# 7006268-0.net
KiCad netlist of a schematic drawn in EAGLE
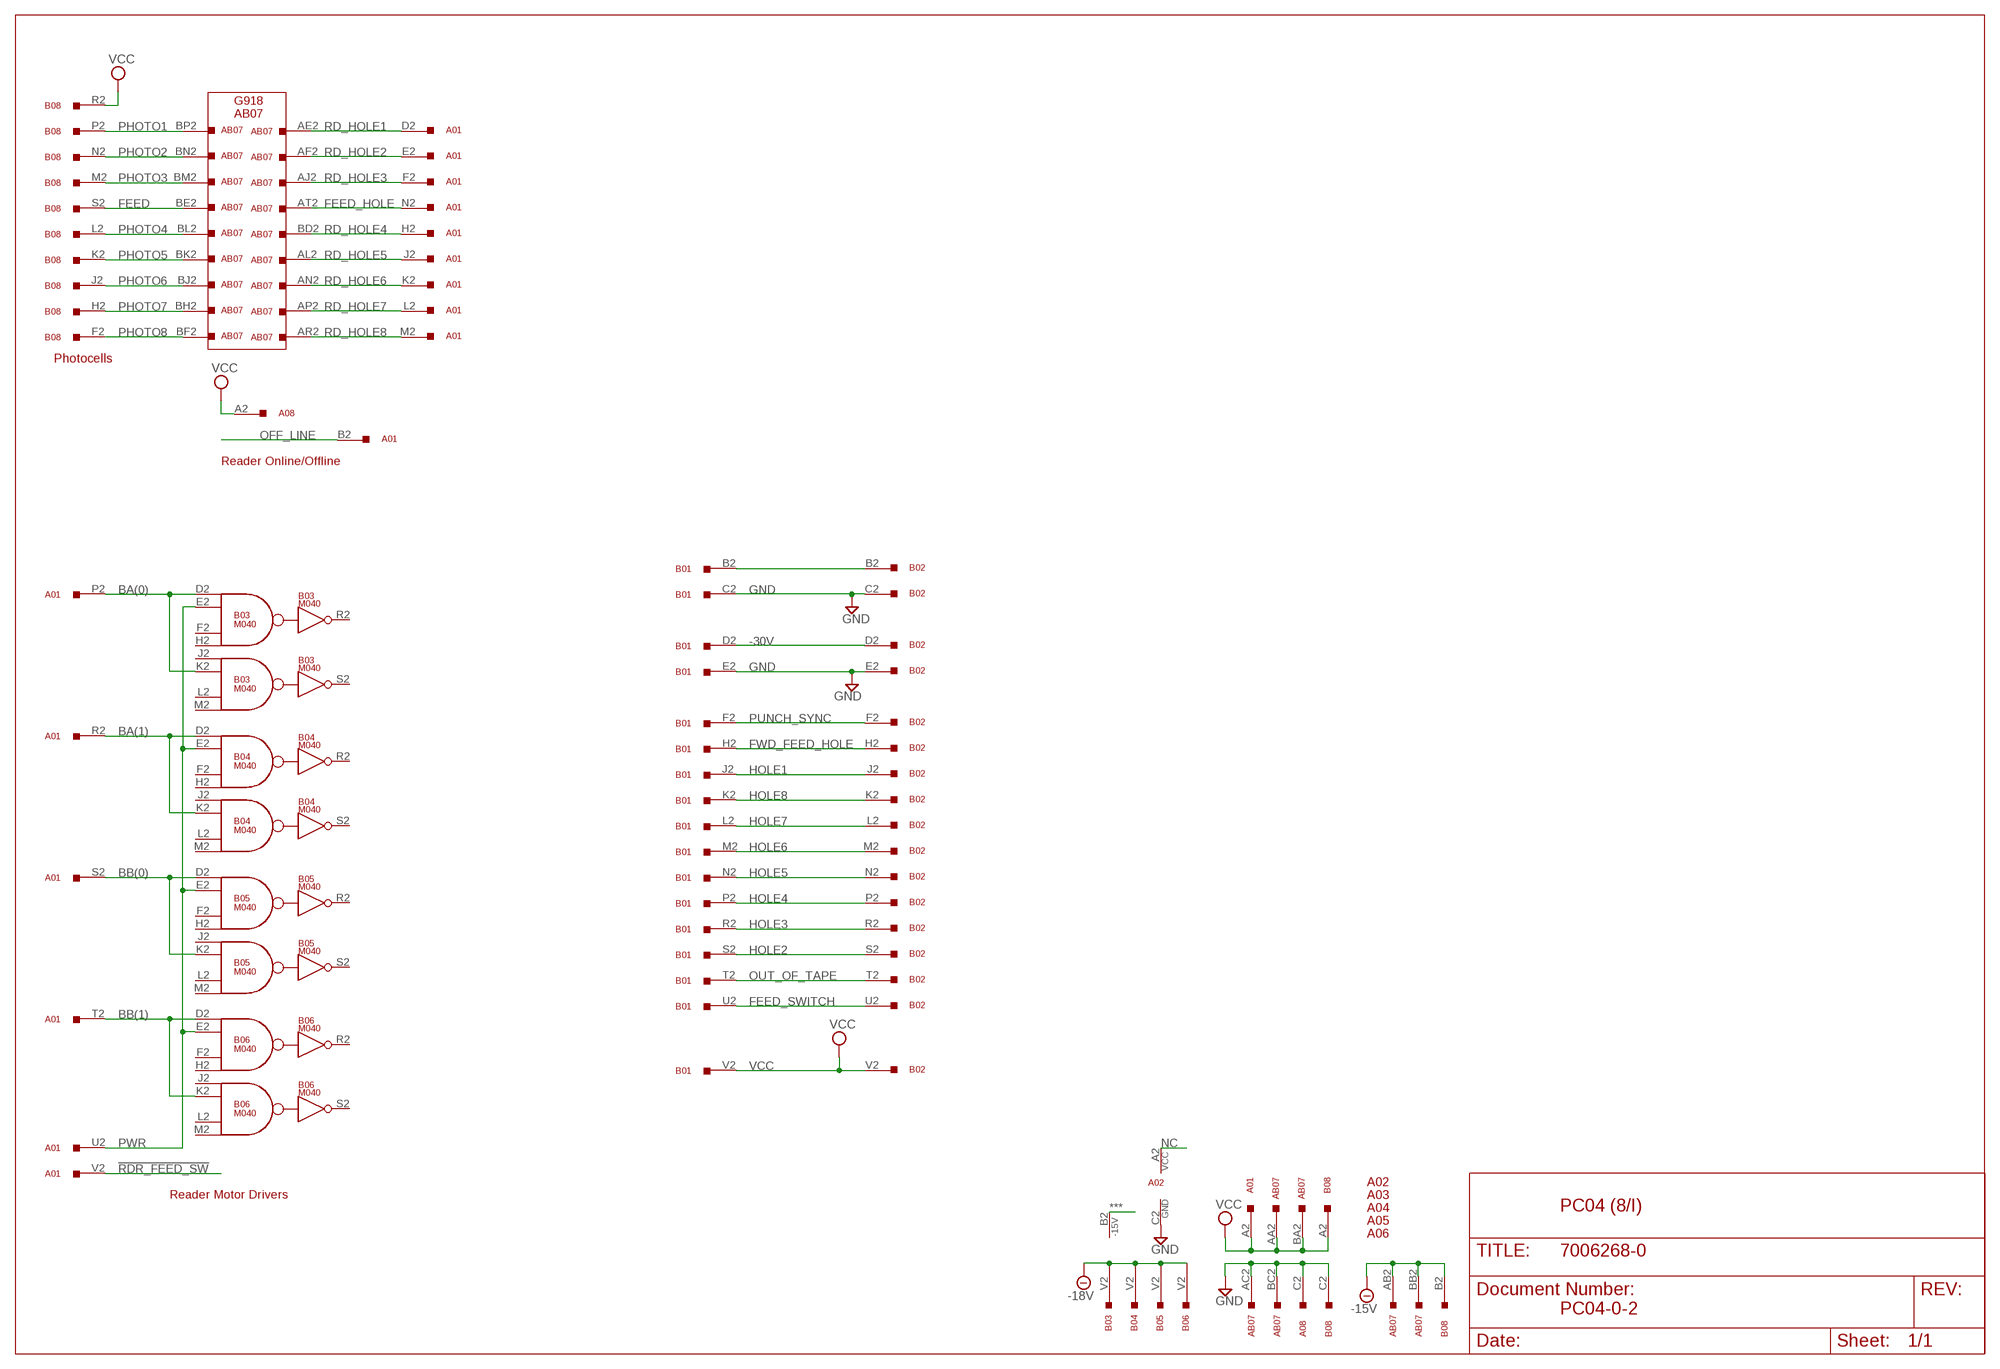
[diagram p0: schematic, sheet 1]

(export (version "E")
  (design (tool "Eeschema 10.0.6"))
  (components
    (comp (ref "A01")
      (value "W033")
      (footprint "eagle-import:H807")
      (libsource (lib "eagle-import") (part "W023"))
    )
    (comp (ref "A02")
      (value "EMPTY")
      (footprint "eagle-import:H807")
      (libsource (lib "eagle-import") (part "EMPTY"))
    )
    (comp (ref "A03")
      (value "EMPTY")
      (footprint "eagle-import:H807")
      (libsource (lib "eagle-import") (part "EMPTY"))
    )
    (comp (ref "A04")
      (value "EMPTY")
      (footprint "eagle-import:H807")
      (libsource (lib "eagle-import") (part "EMPTY"))
    )
    (comp (ref "A05")
      (value "EMPTY")
      (footprint "eagle-import:H807")
      (libsource (lib "eagle-import") (part "EMPTY"))
    )
    (comp (ref "A06")
      (value "EMPTY")
      (footprint "eagle-import:H807")
      (libsource (lib "eagle-import") (part "EMPTY"))
    )
    (comp (ref "A08")
      (value "W033")
      (footprint "eagle-import:H807")
      (libsource (lib "eagle-import") (part "W023"))
    )
    (comp (ref "AB07")
      (value "G918")
      (footprint "eagle-import:H807-2")
      (libsource (lib "eagle-import") (part "W991"))
    )
    (comp (ref "B01")
      (value "W033")
      (footprint "eagle-import:H807")
      (libsource (lib "eagle-import") (part "W023"))
    )
    (comp (ref "B02")
      (value "W033")
      (footprint "eagle-import:H807")
      (libsource (lib "eagle-import") (part "W023"))
    )
    (comp (ref "B03")
      (value "M040")
      (footprint "eagle-import:H807")
      (libsource (lib "eagle-import") (part "M040"))
    )
    (comp (ref "B04")
      (value "M040")
      (footprint "eagle-import:H807")
      (libsource (lib "eagle-import") (part "M040"))
    )
    (comp (ref "B05")
      (value "M040")
      (footprint "eagle-import:H807")
      (libsource (lib "eagle-import") (part "M040"))
    )
    (comp (ref "B06")
      (value "M040")
      (footprint "eagle-import:H807")
      (libsource (lib "eagle-import") (part "M040"))
    )
    (comp (ref "B08")
      (value "W033")
      (footprint "eagle-import:H807")
      (libsource (lib "eagle-import") (part "W023"))
    )
  )
  (nets
    (net (code "1") (name "-15V") (class "Default")
      (node (ref "AB07") (pin "AB2") (pinfunction "P$2_AB2") (pintype "bidirectional"))
      (node (ref "AB07") (pin "BB2") (pinfunction "P$2_BB2") (pintype "bidirectional"))
      (node (ref "B08") (pin "B2") (pinfunction "P$2_B2") (pintype "bidirectional"))
    )
    (net (code "2") (name "-18V") (class "Default")
      (node (ref "B03") (pin "V2") (pinfunction "P$1_V2") (pintype "input"))
      (node (ref "B04") (pin "V2") (pinfunction "P$1_V2") (pintype "input"))
      (node (ref "B05") (pin "V2") (pinfunction "P$1_V2") (pintype "input"))
      (node (ref "B06") (pin "V2") (pinfunction "P$1_V2") (pintype "input"))
    )
    (net (code "3") (name "/***") (class "Default")
      (node (ref "A02") (pin "B2") (pinfunction "-15V_B2") (pintype "power_in"))
    )
    (net (code "4") (name "/-30V") (class "Default")
      (node (ref "B01") (pin "D2") (pinfunction "P$2_D2") (pintype "bidirectional"))
      (node (ref "B02") (pin "D2") (pinfunction "P$2_D2") (pintype "bidirectional"))
    )
    (net (code "5") (name "/BA(0)") (class "Default")
      (node (ref "A01") (pin "P2") (pinfunction "P$2_P2") (pintype "bidirectional"))
      (node (ref "B03") (pin "D2") (pinfunction "D_D2") (pintype "input"))
      (node (ref "B03") (pin "K2") (pinfunction "E_K2") (pintype "input"))
    )
    (net (code "6") (name "/BA(1)") (class "Default")
      (node (ref "A01") (pin "R2") (pinfunction "P$2_R2") (pintype "bidirectional"))
      (node (ref "B04") (pin "D2") (pinfunction "D_D2") (pintype "input"))
      (node (ref "B04") (pin "K2") (pinfunction "E_K2") (pintype "input"))
    )
    (net (code "7") (name "/BB(0)") (class "Default")
      (node (ref "A01") (pin "S2") (pinfunction "P$2_S2") (pintype "bidirectional"))
      (node (ref "B05") (pin "D2") (pinfunction "D_D2") (pintype "input"))
      (node (ref "B05") (pin "K2") (pinfunction "E_K2") (pintype "input"))
    )
    (net (code "8") (name "/BB(1)") (class "Default")
      (node (ref "A01") (pin "T2") (pinfunction "P$2_T2") (pintype "bidirectional"))
      (node (ref "B06") (pin "D2") (pinfunction "D_D2") (pintype "input"))
      (node (ref "B06") (pin "K2") (pinfunction "E_K2") (pintype "input"))
    )
    (net (code "9") (name "/FEED") (class "Default")
      (node (ref "AB07") (pin "BE2") (pinfunction "P$2_BE2") (pintype "bidirectional"))
      (node (ref "B08") (pin "S2") (pinfunction "P$2_S2") (pintype "bidirectional"))
    )
    (net (code "10") (name "/FEED_HOLE") (class "Default")
      (node (ref "A01") (pin "N2") (pinfunction "P$2_N2") (pintype "bidirectional"))
      (node (ref "AB07") (pin "AT2") (pinfunction "P$2_AT2") (pintype "bidirectional"))
    )
    (net (code "11") (name "/FEED_SWITCH") (class "Default")
      (node (ref "B01") (pin "U2") (pinfunction "P$2_U2") (pintype "bidirectional"))
      (node (ref "B02") (pin "U2") (pinfunction "P$2_U2") (pintype "bidirectional"))
    )
    (net (code "12") (name "/FWD_FEED_HOLE") (class "Default")
      (node (ref "B01") (pin "H2") (pinfunction "P$2_H2") (pintype "bidirectional"))
      (node (ref "B02") (pin "H2") (pinfunction "P$2_H2") (pintype "bidirectional"))
    )
    (net (code "13") (name "/HOLE1") (class "Default")
      (node (ref "B01") (pin "J2") (pinfunction "P$2_J2") (pintype "bidirectional"))
      (node (ref "B02") (pin "J2") (pinfunction "P$2_J2") (pintype "bidirectional"))
    )
    (net (code "14") (name "/HOLE2") (class "Default")
      (node (ref "B01") (pin "S2") (pinfunction "P$2_S2") (pintype "bidirectional"))
      (node (ref "B02") (pin "S2") (pinfunction "P$2_S2") (pintype "bidirectional"))
    )
    (net (code "15") (name "/HOLE3") (class "Default")
      (node (ref "B01") (pin "R2") (pinfunction "P$2_R2") (pintype "bidirectional"))
      (node (ref "B02") (pin "R2") (pinfunction "P$2_R2") (pintype "bidirectional"))
    )
    (net (code "16") (name "/HOLE4") (class "Default")
      (node (ref "B01") (pin "P2") (pinfunction "P$2_P2") (pintype "bidirectional"))
      (node (ref "B02") (pin "P2") (pinfunction "P$2_P2") (pintype "bidirectional"))
    )
    (net (code "17") (name "/HOLE5") (class "Default")
      (node (ref "B01") (pin "N2") (pinfunction "P$2_N2") (pintype "bidirectional"))
      (node (ref "B02") (pin "N2") (pinfunction "P$2_N2") (pintype "bidirectional"))
    )
    (net (code "18") (name "/HOLE6") (class "Default")
      (node (ref "B01") (pin "M2") (pinfunction "P$2_M2") (pintype "bidirectional"))
      (node (ref "B02") (pin "M2") (pinfunction "P$2_M2") (pintype "bidirectional"))
    )
    (net (code "19") (name "/HOLE7") (class "Default")
      (node (ref "B01") (pin "L2") (pinfunction "P$2_L2") (pintype "bidirectional"))
      (node (ref "B02") (pin "L2") (pinfunction "P$2_L2") (pintype "bidirectional"))
    )
    (net (code "20") (name "/HOLE8") (class "Default")
      (node (ref "B01") (pin "K2") (pinfunction "P$2_K2") (pintype "bidirectional"))
      (node (ref "B02") (pin "K2") (pinfunction "P$2_K2") (pintype "bidirectional"))
    )
    (net (code "21") (name "/NC") (class "Default")
      (node (ref "A02") (pin "A2") (pinfunction "VCC_A2") (pintype "power_in"))
    )
    (net (code "22") (name "/OFF_LINE") (class "Default")
      (node (ref "A01") (pin "B2") (pinfunction "P$2_B2") (pintype "bidirectional"))
    )
    (net (code "23") (name "/OUT_OF_TAPE") (class "Default")
      (node (ref "B01") (pin "T2") (pinfunction "P$2_T2") (pintype "bidirectional"))
      (node (ref "B02") (pin "T2") (pinfunction "P$2_T2") (pintype "bidirectional"))
    )
    (net (code "24") (name "/PHOTO1") (class "Default")
      (node (ref "AB07") (pin "BP2") (pinfunction "P$2_BP2") (pintype "bidirectional"))
      (node (ref "B08") (pin "P2") (pinfunction "P$2_P2") (pintype "bidirectional"))
    )
    (net (code "25") (name "/PHOTO2") (class "Default")
      (node (ref "AB07") (pin "BN2") (pinfunction "P$2_BN2") (pintype "bidirectional"))
      (node (ref "B08") (pin "N2") (pinfunction "P$2_N2") (pintype "bidirectional"))
    )
    (net (code "26") (name "/PHOTO3") (class "Default")
      (node (ref "AB07") (pin "BM2") (pinfunction "P$2_BM2") (pintype "bidirectional"))
      (node (ref "B08") (pin "M2") (pinfunction "P$2_M2") (pintype "bidirectional"))
    )
    (net (code "27") (name "/PHOTO4") (class "Default")
      (node (ref "AB07") (pin "BL2") (pinfunction "P$2_BL2") (pintype "bidirectional"))
      (node (ref "B08") (pin "L2") (pinfunction "P$2_L2") (pintype "bidirectional"))
    )
    (net (code "28") (name "/PHOTO5") (class "Default")
      (node (ref "AB07") (pin "BK2") (pinfunction "P$2_BK2") (pintype "bidirectional"))
      (node (ref "B08") (pin "K2") (pinfunction "P$2_K2") (pintype "bidirectional"))
    )
    (net (code "29") (name "/PHOTO6") (class "Default")
      (node (ref "AB07") (pin "BJ2") (pinfunction "P$2_BJ2") (pintype "bidirectional"))
      (node (ref "B08") (pin "J2") (pinfunction "P$2_J2") (pintype "bidirectional"))
    )
    (net (code "30") (name "/PHOTO7") (class "Default")
      (node (ref "AB07") (pin "BH2") (pinfunction "P$2_BH2") (pintype "bidirectional"))
      (node (ref "B08") (pin "H2") (pinfunction "P$2_H2") (pintype "bidirectional"))
    )
    (net (code "31") (name "/PHOTO8") (class "Default")
      (node (ref "AB07") (pin "BF2") (pinfunction "P$2_BF2") (pintype "bidirectional"))
      (node (ref "B08") (pin "F2") (pinfunction "P$2_F2") (pintype "bidirectional"))
    )
    (net (code "32") (name "/PUNCH_SYNC") (class "Default")
      (node (ref "B01") (pin "F2") (pinfunction "P$2_F2") (pintype "bidirectional"))
      (node (ref "B02") (pin "F2") (pinfunction "P$2_F2") (pintype "bidirectional"))
    )
    (net (code "33") (name "/PWR") (class "Default")
      (node (ref "A01") (pin "U2") (pinfunction "P$2_U2") (pintype "bidirectional"))
      (node (ref "B03") (pin "E2") (pinfunction "E_E2") (pintype "input"))
      (node (ref "B04") (pin "E2") (pinfunction "E_E2") (pintype "input"))
      (node (ref "B05") (pin "E2") (pinfunction "E_E2") (pintype "input"))
      (node (ref "B06") (pin "E2") (pinfunction "E_E2") (pintype "input"))
    )
    (net (code "34") (name "/RD_HOLE1") (class "Default")
      (node (ref "A01") (pin "D2") (pinfunction "P$2_D2") (pintype "bidirectional"))
      (node (ref "AB07") (pin "AE2") (pinfunction "P$2_AE2") (pintype "bidirectional"))
    )
    (net (code "35") (name "/RD_HOLE2") (class "Default")
      (node (ref "A01") (pin "E2") (pinfunction "P$2_E2") (pintype "bidirectional"))
      (node (ref "AB07") (pin "AF2") (pinfunction "P$2_AF2") (pintype "bidirectional"))
    )
    (net (code "36") (name "/RD_HOLE3") (class "Default")
      (node (ref "A01") (pin "F2") (pinfunction "P$2_F2") (pintype "bidirectional"))
      (node (ref "AB07") (pin "AJ2") (pinfunction "P$2_AJ2") (pintype "bidirectional"))
    )
    (net (code "37") (name "/RD_HOLE4") (class "Default")
      (node (ref "A01") (pin "H2") (pinfunction "P$2_H2") (pintype "bidirectional"))
      (node (ref "AB07") (pin "BD2") (pinfunction "P$2_BD2") (pintype "bidirectional"))
    )
    (net (code "38") (name "/RD_HOLE5") (class "Default")
      (node (ref "A01") (pin "J2") (pinfunction "P$2_J2") (pintype "bidirectional"))
      (node (ref "AB07") (pin "AL2") (pinfunction "P$2_AL2") (pintype "bidirectional"))
    )
    (net (code "39") (name "/RD_HOLE6") (class "Default")
      (node (ref "A01") (pin "K2") (pinfunction "P$2_K2") (pintype "bidirectional"))
      (node (ref "AB07") (pin "AN2") (pinfunction "P$2_AN2") (pintype "bidirectional"))
    )
    (net (code "40") (name "/RD_HOLE7") (class "Default")
      (node (ref "A01") (pin "L2") (pinfunction "P$2_L2") (pintype "bidirectional"))
      (node (ref "AB07") (pin "AP2") (pinfunction "P$2_AP2") (pintype "bidirectional"))
    )
    (net (code "41") (name "/RD_HOLE8") (class "Default")
      (node (ref "A01") (pin "M2") (pinfunction "P$2_M2") (pintype "bidirectional"))
      (node (ref "AB07") (pin "AR2") (pinfunction "P$2_AR2") (pintype "bidirectional"))
    )
    (net (code "42") (name "/~{RDR_FEED_SW}") (class "Default")
      (node (ref "A01") (pin "V2") (pinfunction "P$2_V2") (pintype "bidirectional"))
    )
    (net (code "43") (name "GND") (class "Default")
      (node (ref "A02") (pin "C2") (pinfunction "GND_C2") (pintype "power_in"))
      (node (ref "A08") (pin "C2") (pinfunction "P$2_C2") (pintype "bidirectional"))
      (node (ref "AB07") (pin "AC2") (pinfunction "P$2_AC2") (pintype "bidirectional"))
      (node (ref "AB07") (pin "BC2") (pinfunction "P$2_BC2") (pintype "bidirectional"))
      (node (ref "B01") (pin "C2") (pinfunction "P$2_C2") (pintype "bidirectional"))
      (node (ref "B01") (pin "E2") (pinfunction "P$2_E2") (pintype "bidirectional"))
      (node (ref "B02") (pin "C2") (pinfunction "P$2_C2") (pintype "bidirectional"))
      (node (ref "B02") (pin "E2") (pinfunction "P$2_E2") (pintype "bidirectional"))
      (node (ref "B08") (pin "C2") (pinfunction "P$2_C2") (pintype "bidirectional"))
    )
    (net (code "44") (name "Net-(B01B-P$2)") (class "Default")
      (node (ref "B01") (pin "B2") (pinfunction "P$2_B2") (pintype "bidirectional"))
      (node (ref "B02") (pin "B2") (pinfunction "P$2_B2") (pintype "bidirectional"))
    )
    (net (code "45") (name "VCC") (class "Default")
      (node (ref "A01") (pin "A2") (pinfunction "P$2_A2") (pintype "bidirectional"))
      (node (ref "A08") (pin "A2") (pinfunction "P$2_A2") (pintype "bidirectional"))
      (node (ref "AB07") (pin "AA2") (pinfunction "P$2_AA2") (pintype "bidirectional"))
      (node (ref "AB07") (pin "BA2") (pinfunction "P$2_BA2") (pintype "bidirectional"))
      (node (ref "B01") (pin "V2") (pinfunction "P$2_V2") (pintype "bidirectional"))
      (node (ref "B02") (pin "V2") (pinfunction "P$2_V2") (pintype "bidirectional"))
      (node (ref "B08") (pin "A2") (pinfunction "P$2_A2") (pintype "bidirectional"))
      (node (ref "B08") (pin "R2") (pinfunction "P$2_R2") (pintype "bidirectional"))
    )
    (net (code "46") (name "unconnected-(B03A-F-PadF2)") (class "Default")
      (node (ref "B03") (pin "F2") (pinfunction "F_F2") (pintype "input"))
    )
    (net (code "47") (name "unconnected-(B03A-H-PadH2)") (class "Default")
      (node (ref "B03") (pin "H2") (pinfunction "H_H2") (pintype "input"))
    )
    (net (code "48") (name "unconnected-(B03A-R-PadR2)") (class "Default")
      (node (ref "B03") (pin "R2") (pinfunction "R_R2") (pintype "open_collector"))
    )
    (net (code "49") (name "unconnected-(B03B-D-PadJ2)") (class "Default")
      (node (ref "B03") (pin "J2") (pinfunction "D_J2") (pintype "input"))
    )
    (net (code "50") (name "unconnected-(B03B-F-PadL2)") (class "Default")
      (node (ref "B03") (pin "L2") (pinfunction "F_L2") (pintype "input"))
    )
    (net (code "51") (name "unconnected-(B03B-H-PadM2)") (class "Default")
      (node (ref "B03") (pin "M2") (pinfunction "H_M2") (pintype "input"))
    )
    (net (code "52") (name "unconnected-(B03B-R-PadS2)") (class "Default")
      (node (ref "B03") (pin "S2") (pinfunction "R_S2") (pintype "open_collector"))
    )
    (net (code "53") (name "unconnected-(B04A-F-PadF2)") (class "Default")
      (node (ref "B04") (pin "F2") (pinfunction "F_F2") (pintype "input"))
    )
    (net (code "54") (name "unconnected-(B04A-H-PadH2)") (class "Default")
      (node (ref "B04") (pin "H2") (pinfunction "H_H2") (pintype "input"))
    )
    (net (code "55") (name "unconnected-(B04A-R-PadR2)") (class "Default")
      (node (ref "B04") (pin "R2") (pinfunction "R_R2") (pintype "open_collector"))
    )
    (net (code "56") (name "unconnected-(B04B-D-PadJ2)") (class "Default")
      (node (ref "B04") (pin "J2") (pinfunction "D_J2") (pintype "input"))
    )
    (net (code "57") (name "unconnected-(B04B-F-PadL2)") (class "Default")
      (node (ref "B04") (pin "L2") (pinfunction "F_L2") (pintype "input"))
    )
    (net (code "58") (name "unconnected-(B04B-H-PadM2)") (class "Default")
      (node (ref "B04") (pin "M2") (pinfunction "H_M2") (pintype "input"))
    )
    (net (code "59") (name "unconnected-(B04B-R-PadS2)") (class "Default")
      (node (ref "B04") (pin "S2") (pinfunction "R_S2") (pintype "open_collector"))
    )
    (net (code "60") (name "unconnected-(B05A-F-PadF2)") (class "Default")
      (node (ref "B05") (pin "F2") (pinfunction "F_F2") (pintype "input"))
    )
    (net (code "61") (name "unconnected-(B05A-H-PadH2)") (class "Default")
      (node (ref "B05") (pin "H2") (pinfunction "H_H2") (pintype "input"))
    )
    (net (code "62") (name "unconnected-(B05A-R-PadR2)") (class "Default")
      (node (ref "B05") (pin "R2") (pinfunction "R_R2") (pintype "open_collector"))
    )
    (net (code "63") (name "unconnected-(B05B-D-PadJ2)") (class "Default")
      (node (ref "B05") (pin "J2") (pinfunction "D_J2") (pintype "input"))
    )
    (net (code "64") (name "unconnected-(B05B-F-PadL2)") (class "Default")
      (node (ref "B05") (pin "L2") (pinfunction "F_L2") (pintype "input"))
    )
    (net (code "65") (name "unconnected-(B05B-H-PadM2)") (class "Default")
      (node (ref "B05") (pin "M2") (pinfunction "H_M2") (pintype "input"))
    )
    (net (code "66") (name "unconnected-(B05B-R-PadS2)") (class "Default")
      (node (ref "B05") (pin "S2") (pinfunction "R_S2") (pintype "open_collector"))
    )
    (net (code "67") (name "unconnected-(B06A-F-PadF2)") (class "Default")
      (node (ref "B06") (pin "F2") (pinfunction "F_F2") (pintype "input"))
    )
    (net (code "68") (name "unconnected-(B06A-H-PadH2)") (class "Default")
      (node (ref "B06") (pin "H2") (pinfunction "H_H2") (pintype "input"))
    )
    (net (code "69") (name "unconnected-(B06A-R-PadR2)") (class "Default")
      (node (ref "B06") (pin "R2") (pinfunction "R_R2") (pintype "open_collector"))
    )
    (net (code "70") (name "unconnected-(B06B-D-PadJ2)") (class "Default")
      (node (ref "B06") (pin "J2") (pinfunction "D_J2") (pintype "input"))
    )
    (net (code "71") (name "unconnected-(B06B-F-PadL2)") (class "Default")
      (node (ref "B06") (pin "L2") (pinfunction "F_L2") (pintype "input"))
    )
    (net (code "72") (name "unconnected-(B06B-H-PadM2)") (class "Default")
      (node (ref "B06") (pin "M2") (pinfunction "H_M2") (pintype "input"))
    )
    (net (code "73") (name "unconnected-(B06B-R-PadS2)") (class "Default")
      (node (ref "B06") (pin "S2") (pinfunction "R_S2") (pintype "open_collector"))
    )
  )
)
